# Hydroponics_Schematic.net
KiCad netlist of a schematic drawn in Altium Designer
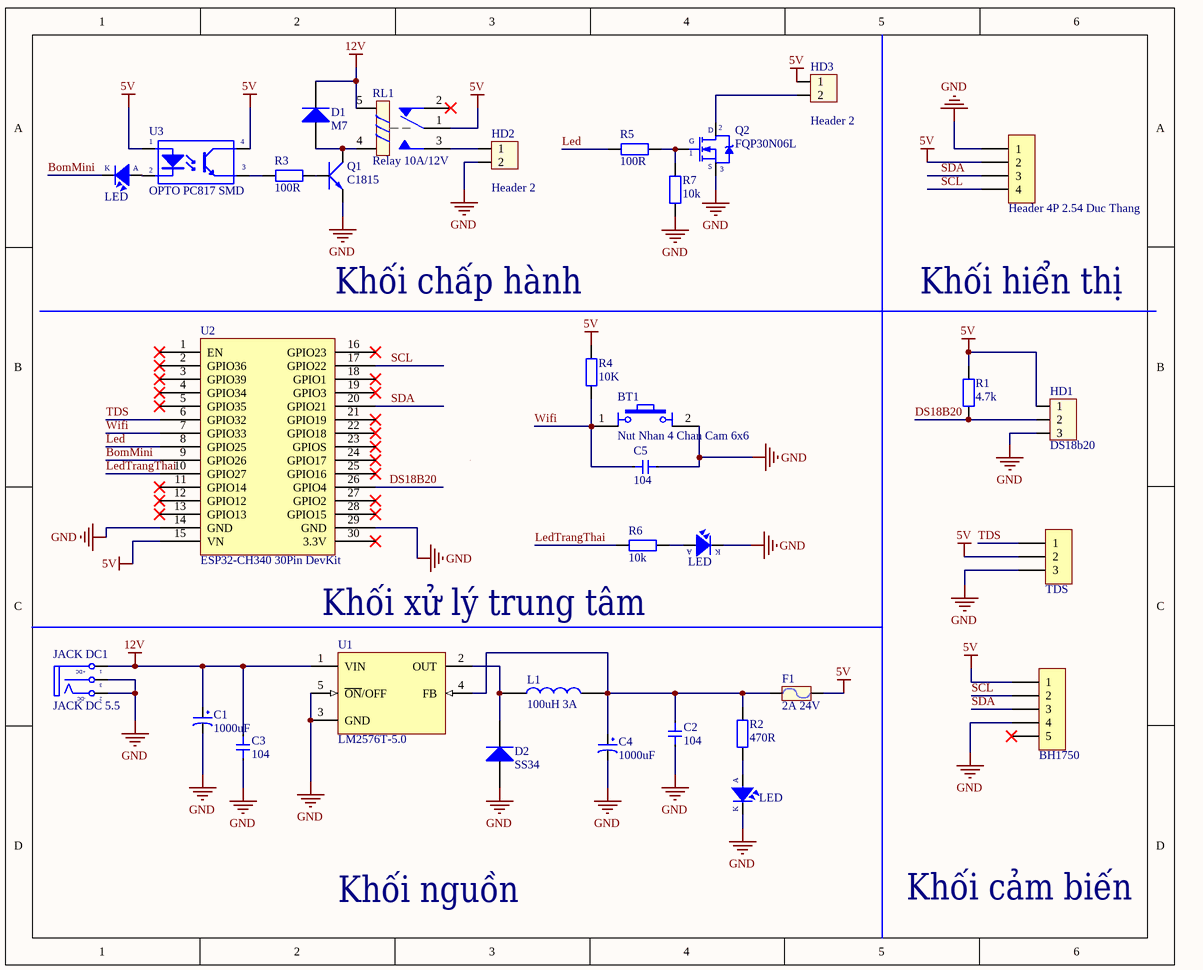
[diagram p0: Hydroponics_Schematic.SchDoc]

(export (version "E")
  (design (tool "Eeschema 10.0.6"))
  (components
    (comp (ref "BT1")
      (value "Nut Nhan 4 Chan Cam 6x6")
      (footprint "Nut Nhan 4 Chan Cam 6x6")
      (description "Nut Nhan 4 Chan 6x6mm")
      (libsource (lib "ThuvienAltiumFULLHD") (part "Nut Nhan 4 Chan Cam 6x6"))
    )
    (comp (ref "C1")
      (value "1000uF")
      (footprint "tu hoa 10mm")
      (description "Cắm")
      (libsource (lib "ThuvienAltiumFULLHD") (part "Tu Hoa 1000uF 10V 10x12"))
    )
    (comp (ref "C2")
      (value "104")
      (footprint "Cap 0805")
      (description "Capacitor SMD 0805")
      (libsource (lib "ThuvienAltiumFULLHD") (part "Cap 0805"))
    )
    (comp (ref "C3")
      (value "104")
      (footprint "Cap 0805")
      (description "Capacitor SMD 0805")
      (libsource (lib "ThuvienAltiumFULLHD") (part "Cap 0805"))
    )
    (comp (ref "C4")
      (value "1000uF")
      (footprint "tu hoa 10mm")
      (description "Cắm")
      (libsource (lib "ThuvienAltiumFULLHD") (part "Tu Hoa 1000uF 10V 10x12"))
    )
    (comp (ref "C5")
      (value "104")
      (footprint "Cap 0805")
      (description "Capacitor SMD 0805")
      (libsource (lib "ThuvienAltiumFULLHD") (part "Cap 0805"))
    )
    (comp (ref "D1")
      (value "M7")
      (footprint "DIODE SMA")
      (description "Dán")
      (libsource (lib "ThuvienAltiumFULLHD") (part "Diode M7 ( 4007 )"))
    )
    (comp (ref "D2")
      (value "SS34")
      (footprint "DIODE SMA")
      (description "Dán")
      (libsource (lib "ThuvienAltiumFULLHD") (part "Diode SS34 ( 1N5822 )"))
    )
    (comp (ref "F1")
      (value "2A 24V")
      (footprint "Cau chi tu phuc hoi 2A 24V SMD1812")
      (description "2A 24V SMD1812")
      (libsource (lib "ThuvienAltiumFULLHD") (part "Cau chi tu phuc hoi 2A 24V SMD1812"))
    )
    (comp (ref "H1")
      (value "BH1750")
      (footprint "XH2.54M-5")
      (description "Cắm")
      (libsource (lib "ThuvienAltiumFULLHD") (part "Header 5P 2.54 Duc Thang"))
    )
    (comp (ref "H2")
      (value "TDS")
      (footprint "XH2.54M-3")
      (description "Cắm")
      (libsource (lib "ThuvienAltiumFULLHD") (part "Header 3P 2.54 Duc Thang"))
    )
    (comp (ref "H3")
      (value "Header 4P 2.54 Duc Thang")
      (footprint "XH2.54M-4")
      (description "Cắm")
      (libsource (lib "ThuvienAltiumFULLHD") (part "Header 4P 2.54 Duc Thang"))
    )
    (comp (ref "HD1")
      (value "DS18b20")
      (footprint "KF127-3P")
      (description "Header 3 (Green)")
      (libsource (lib "PART_VDE") (part "Hed3"))
    )
    (comp (ref "HD2")
      (value "Header 2")
      (footprint "HED2")
      (description "Header 2 (Green)")
      (libsource (lib "PART_VDE") (part "Hed2"))
    )
    (comp (ref "HD3")
      (value "Header 2")
      (footprint "HED2")
      (description "Header 2 (Green)")
      (libsource (lib "PART_VDE") (part "Hed2"))
    )
    (comp (ref "JACK DC1")
      (value "JACK DC 5.5")
      (footprint "JACK DC 5.5")
      (libsource (lib "ThuvienAltiumFULLHD") (part "JACK DC 5.5"))
    )
    (comp (ref "L1")
      (value "100uH 3A")
      (footprint "CUON CAM 100uH3A")
      (description "Dán")
      (libsource (lib "ThuvienAltiumFULLHD") (part "CUON CAM 100uH DIP"))
    )
    (comp (ref "LED1")
      (value "LED")
      (footprint "LED-3")
      (description "LED Single colour Green and Red")
      (libsource (lib "ThuvienAltiumFULLHD") (part "LED"))
    )
    (comp (ref "LED2")
      (value "LED")
      (footprint "LED-3")
      (description "LED Single colour Green and Red")
      (libsource (lib "ThuvienAltiumFULLHD") (part "LED"))
    )
    (comp (ref "LED3")
      (value "LED")
      (footprint "LED-3")
      (description "LED Single colour Green and Red")
      (libsource (lib "ThuvienAltiumFULLHD") (part "LED"))
    )
    (comp (ref "Q1")
      (value "C1815")
      (footprint "QTO-92")
      (description "NPN 600mW, ECB")
      (libsource (lib "PART_VDE") (part "C1815"))
    )
    (comp (ref "Q2")
      (value "FQP30N06L")
      (footprint "QTO-220")
      (description "MOSFET N - CHANNEL 500V - 0.75 - 8A - TO-220")
      (libsource (lib "PART_VDE") (part "IRF840"))
    )
    (comp (ref "R1")
      (value "4.7k")
      (footprint "Tro SMD 0805")
      (description "Dán")
      (libsource (lib "ThuvienAltiumFULLHD") (part "Tro 0805 5% 470R"))
    )
    (comp (ref "R2")
      (value "470R")
      (footprint "Tro SMD 0805")
      (description "Dán")
      (libsource (lib "ThuvienAltiumFULLHD") (part "Tro 0805 5% 470R"))
    )
    (comp (ref "R3")
      (value "100R")
      (footprint "Tro SMD 0805")
      (description "Dán")
      (libsource (lib "ThuvienAltiumFULLHD") (part "Tro 0805 5% 470R"))
    )
    (comp (ref "R4")
      (value "10K")
      (footprint "Tro SMD 0805")
      (description "Dán")
      (libsource (lib "ThuvienAltiumFULLHD") (part "Tro 0805 5% 470R"))
    )
    (comp (ref "R5")
      (value "100R")
      (footprint "Tro SMD 0805")
      (description "Dán")
      (libsource (lib "ThuvienAltiumFULLHD") (part "Tro 0805 5% 470R"))
    )
    (comp (ref "R6")
      (value "10k")
      (footprint "Tro SMD 0805")
      (description "Dán")
      (libsource (lib "ThuvienAltiumFULLHD") (part "Tro 0805 5% 470R"))
    )
    (comp (ref "R7")
      (value "10k")
      (footprint "Tro SMD 0805")
      (description "Dán")
      (libsource (lib "ThuvienAltiumFULLHD") (part "Tro 0805 5% 470R"))
    )
    (comp (ref "RL1")
      (value "Relay 10A/12V")
      (footprint "RL_SPDT_10A")
      (description "Relay SPDT,10A - 12VDC 5 Pin")
      (libsource (lib "ThuvienAltiumFULLHD") (part "Relay 1"))
    )
    (comp (ref "U1")
      (value "LM2576T-5.0")
      (footprint "LM2576t")
      (description "SIMPLE SWITCHER; 3A Step-Down Voltage Regulator")
      (fields
        (field (name "MANUFACTURER") "National Semiconductor")
        (field (name "DIGIKEYPARTNUMBER") "LM2576T-5.0-ND")
        (field (name "PUBLISHER") "Altium Limited")
      )
      (libsource (lib "ThuvienAltiumFULLHD") (part "LM2576T-5.0"))
    )
    (comp (ref "U2")
      (value "ESP32-CH340 30Pin DevKit")
      (footprint "DIP30")
      (description "ESP32 DevKit V1 (CH340, 30 pins, 3.3V)")
      (libsource (lib "Schlib1") (part "Component_1"))
    )
    (comp (ref "U3")
      (value "OPTO PC817 SMD")
      (footprint "SOP4")
      (description "Single Opto")
      (libsource (lib "ThuvienAltiumFULLHD") (part "OPTO PC817 SMD"))
    )
  )
  (nets
    (net (code "1") (name "/BomMini") (class "Default")
      (node (ref "LED3") (pin "2") (pinfunction "K_2") (pintype "passive"))
      (node (ref "U2") (pin "9") (pinfunction "GPIO26_9") (pintype "passive"))
    )
    (net (code "2") (name "/DS18B20") (class "Default")
      (node (ref "HD1") (pin "2") (pinfunction "2_2") (pintype "passive"))
      (node (ref "R1") (pin "2") (pinfunction "2_2") (pintype "passive"))
      (node (ref "U2") (pin "26") (pinfunction "GPIO4_26") (pintype "passive"))
    )
    (net (code "3") (name "/Led") (class "Default")
      (node (ref "R5") (pin "1") (pinfunction "1_1") (pintype "passive"))
      (node (ref "U2") (pin "8") (pinfunction "GPIO25_8") (pintype "passive"))
    )
    (net (code "4") (name "/LedTrangThai") (class "Default")
      (node (ref "R6") (pin "2") (pinfunction "2_2") (pintype "passive"))
      (node (ref "U2") (pin "10") (pinfunction "GPIO27_10") (pintype "passive"))
    )
    (net (code "5") (name "/SCL") (class "Default")
      (node (ref "H1") (pin "2") (pinfunction "2_2") (pintype "passive"))
      (node (ref "H3") (pin "4") (pinfunction "4_4") (pintype "passive"))
      (node (ref "U2") (pin "17") (pinfunction "GPIO22_17") (pintype "passive"))
    )
    (net (code "6") (name "/SDA") (class "Default")
      (node (ref "H1") (pin "3") (pinfunction "3_3") (pintype "passive"))
      (node (ref "H3") (pin "3") (pinfunction "3_3") (pintype "passive"))
      (node (ref "U2") (pin "20") (pinfunction "GPIO21_20") (pintype "passive"))
    )
    (net (code "7") (name "/TDS") (class "Default")
      (node (ref "H2") (pin "1") (pinfunction "1_1") (pintype "passive"))
      (node (ref "U2") (pin "6") (pinfunction "GPIO32_6") (pintype "passive"))
    )
    (net (code "8") (name "/Wifi") (class "Default")
      (node (ref "BT1") (pin "1") (pintype "passive"))
      (node (ref "C5") (pin "1") (pinfunction "1_1") (pintype "passive"))
      (node (ref "R4") (pin "1") (pinfunction "1_1") (pintype "passive"))
      (node (ref "U2") (pin "7") (pinfunction "GPIO33_7") (pintype "passive"))
    )
    (net (code "9") (name "5V") (class "Default")
      (node (ref "F1") (pin "2") (pinfunction "2_2") (pintype "passive"))
      (node (ref "H1") (pin "1") (pinfunction "1_1") (pintype "passive"))
      (node (ref "H2") (pin "2") (pinfunction "2_2") (pintype "passive"))
      (node (ref "H3") (pin "2") (pinfunction "2_2") (pintype "passive"))
      (node (ref "HD1") (pin "1") (pinfunction "1_1") (pintype "passive"))
      (node (ref "HD3") (pin "1") (pinfunction "1_1") (pintype "passive"))
      (node (ref "R1") (pin "1") (pinfunction "1_1") (pintype "passive"))
      (node (ref "R4") (pin "2") (pinfunction "2_2") (pintype "passive"))
      (node (ref "RL1") (pin "1") (pinfunction "1_1") (pintype "passive"))
      (node (ref "U2") (pin "15") (pinfunction "VN_15") (pintype "passive"))
      (node (ref "U3") (pin "1") (pinfunction "A_1") (pintype "passive"))
      (node (ref "U3") (pin "4") (pinfunction "C_4") (pintype "passive"))
    )
    (net (code "10") (name "12V") (class "Default")
      (node (ref "C1") (pin "1") (pinfunction "1_1") (pintype "passive"))
      (node (ref "C3") (pin "1") (pinfunction "1_1") (pintype "passive"))
      (node (ref "D1") (pin "2") (pinfunction "K_2") (pintype "passive"))
      (node (ref "JACK DC1") (pin "1") (pinfunction "T_1") (pintype "passive"))
      (node (ref "RL1") (pin "5") (pinfunction "5_5") (pintype "passive"))
      (node (ref "U1") (pin "1") (pinfunction "VIN_1") (pintype "power_in"))
    )
    (net (code "11") (name "GND") (class "Default")
      (node (ref "BT1") (pin "2") (pintype "passive"))
      (node (ref "C1") (pin "2") (pinfunction "2_2") (pintype "passive"))
      (node (ref "C2") (pin "2") (pinfunction "2_2") (pintype "passive"))
      (node (ref "C3") (pin "2") (pinfunction "2_2") (pintype "passive"))
      (node (ref "C4") (pin "2") (pinfunction "2_2") (pintype "passive"))
      (node (ref "C5") (pin "2") (pinfunction "2_2") (pintype "passive"))
      (node (ref "D2") (pin "1") (pinfunction "A_1") (pintype "passive"))
      (node (ref "H1") (pin "4") (pinfunction "4_4") (pintype "passive"))
      (node (ref "H2") (pin "3") (pinfunction "3_3") (pintype "passive"))
      (node (ref "H3") (pin "1") (pinfunction "1_1") (pintype "passive"))
      (node (ref "HD1") (pin "3") (pinfunction "3_3") (pintype "passive"))
      (node (ref "HD2") (pin "2") (pinfunction "2_2") (pintype "passive"))
      (node (ref "JACK DC1") (pin "2") (pinfunction "TN_2") (pintype "passive"))
      (node (ref "JACK DC1") (pin "3") (pinfunction "S_3") (pintype "power_in"))
      (node (ref "LED1") (pin "2") (pinfunction "K_2") (pintype "passive"))
      (node (ref "LED2") (pin "2") (pinfunction "K_2") (pintype "passive"))
      (node (ref "Q1") (pin "1") (pinfunction "E_1") (pintype "passive"))
      (node (ref "Q2") (pin "3") (pinfunction "S_3") (pintype "passive"))
      (node (ref "R7") (pin "2") (pinfunction "2_2") (pintype "passive"))
      (node (ref "U1") (pin "3") (pinfunction "GND_3") (pintype "power_in"))
      (node (ref "U1") (pin "5") (pinfunction "~{ON}/OFF_5") (pintype "input"))
      (node (ref "U2") (pin "14") (pinfunction "GND_14") (pintype "passive"))
      (node (ref "U2") (pin "29") (pinfunction "GND_29") (pintype "passive"))
    )
    (net (code "12") (name "Net-(D1-A)") (class "Default")
      (node (ref "D1") (pin "1") (pinfunction "A_1") (pintype "passive"))
      (node (ref "Q1") (pin "2") (pinfunction "C_2") (pintype "passive"))
      (node (ref "RL1") (pin "4") (pinfunction "4_4") (pintype "passive"))
    )
    (net (code "13") (name "Net-(D2-K)") (class "Default")
      (node (ref "D2") (pin "2") (pinfunction "K_2") (pintype "passive"))
      (node (ref "L1") (pin "1") (pinfunction "1_1") (pintype "passive"))
      (node (ref "U1") (pin "2") (pinfunction "OUT_2") (pintype "power_in"))
    )
    (net (code "14") (name "Net-(HD2-Pad1)") (class "Default")
      (node (ref "HD2") (pin "1") (pinfunction "1_1") (pintype "passive"))
      (node (ref "RL1") (pin "3") (pinfunction "3_3") (pintype "passive"))
    )
    (net (code "15") (name "Net-(LED1-A)") (class "Default")
      (node (ref "LED1") (pin "1") (pinfunction "A_1") (pintype "passive"))
      (node (ref "R2") (pin "1") (pinfunction "1_1") (pintype "passive"))
    )
    (net (code "16") (name "Net-(LED2-A)") (class "Default")
      (node (ref "LED2") (pin "1") (pinfunction "A_1") (pintype "passive"))
      (node (ref "R6") (pin "1") (pinfunction "1_1") (pintype "passive"))
    )
    (net (code "17") (name "Net-(LED3-A)") (class "Default")
      (node (ref "LED3") (pin "1") (pinfunction "A_1") (pintype "passive"))
      (node (ref "U3") (pin "2") (pinfunction "K_2") (pintype "passive"))
    )
    (net (code "18") (name "Net-(Q1-B)") (class "Default")
      (node (ref "Q1") (pin "3") (pinfunction "B_3") (pintype "passive"))
      (node (ref "R3") (pin "2") (pinfunction "2_2") (pintype "passive"))
    )
    (net (code "19") (name "Net-(Q2-D)") (class "Default")
      (node (ref "HD3") (pin "2") (pinfunction "2_2") (pintype "passive"))
      (node (ref "Q2") (pin "2") (pinfunction "D_2") (pintype "passive"))
    )
    (net (code "20") (name "Net-(Q2-G)") (class "Default")
      (node (ref "Q2") (pin "1") (pinfunction "G_1") (pintype "passive"))
      (node (ref "R5") (pin "2") (pinfunction "2_2") (pintype "passive"))
      (node (ref "R7") (pin "1") (pinfunction "1_1") (pintype "passive"))
    )
    (net (code "21") (name "Net-(U1-FB)") (class "Default")
      (node (ref "C2") (pin "1") (pinfunction "1_1") (pintype "passive"))
      (node (ref "C4") (pin "1") (pinfunction "1_1") (pintype "passive"))
      (node (ref "F1") (pin "1") (pinfunction "1_1") (pintype "passive"))
      (node (ref "L1") (pin "2") (pinfunction "2_2") (pintype "passive"))
      (node (ref "R2") (pin "2") (pinfunction "2_2") (pintype "passive"))
      (node (ref "U1") (pin "4") (pinfunction "FB_4") (pintype "input"))
    )
    (net (code "22") (name "Net-(U3-E)") (class "Default")
      (node (ref "R3") (pin "1") (pinfunction "1_1") (pintype "passive"))
      (node (ref "U3") (pin "3") (pinfunction "E_3") (pintype "passive"))
    )
    (net (code "23") (name "unconnected-(H1-Pad5)") (class "Default")
      (node (ref "H1") (pin "5") (pinfunction "5_5") (pintype "passive+no_connect"))
    )
    (net (code "24") (name "unconnected-(RL1-Pad2)") (class "Default")
      (node (ref "RL1") (pin "2") (pinfunction "2_2") (pintype "passive+no_connect"))
    )
    (net (code "25") (name "unconnected-(U2-3.3V-Pad30)") (class "Default")
      (node (ref "U2") (pin "30") (pinfunction "3.3V_30") (pintype "passive+no_connect"))
    )
    (net (code "26") (name "unconnected-(U2-EN-Pad1)") (class "Default")
      (node (ref "U2") (pin "1") (pinfunction "EN_1") (pintype "passive+no_connect"))
    )
    (net (code "27") (name "unconnected-(U2-GPIO1-Pad18)") (class "Default")
      (node (ref "U2") (pin "18") (pinfunction "GPIO1_18") (pintype "passive+no_connect"))
    )
    (net (code "28") (name "unconnected-(U2-GPIO2-Pad27)") (class "Default")
      (node (ref "U2") (pin "27") (pinfunction "GPIO2_27") (pintype "passive+no_connect"))
    )
    (net (code "29") (name "unconnected-(U2-GPIO3-Pad19)") (class "Default")
      (node (ref "U2") (pin "19") (pinfunction "GPIO3_19") (pintype "passive+no_connect"))
    )
    (net (code "30") (name "unconnected-(U2-GPIO12-Pad12)") (class "Default")
      (node (ref "U2") (pin "12") (pinfunction "GPIO12_12") (pintype "passive+no_connect"))
    )
    (net (code "31") (name "unconnected-(U2-GPIO13-Pad13)") (class "Default")
      (node (ref "U2") (pin "13") (pinfunction "GPIO13_13") (pintype "passive+no_connect"))
    )
    (net (code "32") (name "unconnected-(U2-GPIO14-Pad11)") (class "Default")
      (node (ref "U2") (pin "11") (pinfunction "GPIO14_11") (pintype "passive+no_connect"))
    )
    (net (code "33") (name "unconnected-(U2-GPIO15-Pad28)") (class "Default")
      (node (ref "U2") (pin "28") (pinfunction "GPIO15_28") (pintype "passive+no_connect"))
    )
    (net (code "34") (name "unconnected-(U2-GPIO16-Pad25)") (class "Default")
      (node (ref "U2") (pin "25") (pinfunction "GPIO16_25") (pintype "passive+no_connect"))
    )
    (net (code "35") (name "unconnected-(U2-GPIO17-Pad24)") (class "Default")
      (node (ref "U2") (pin "24") (pinfunction "GPIO17_24") (pintype "passive+no_connect"))
    )
    (net (code "36") (name "unconnected-(U2-GPIO18-Pad22)") (class "Default")
      (node (ref "U2") (pin "22") (pinfunction "GPIO18_22") (pintype "passive+no_connect"))
    )
    (net (code "37") (name "unconnected-(U2-GPIO19-Pad21)") (class "Default")
      (node (ref "U2") (pin "21") (pinfunction "GPIO19_21") (pintype "passive+no_connect"))
    )
    (net (code "38") (name "unconnected-(U2-GPIO23-Pad16)") (class "Default")
      (node (ref "U2") (pin "16") (pinfunction "GPIO23_16") (pintype "passive+no_connect"))
    )
    (net (code "39") (name "unconnected-(U2-GPIO34-Pad4)") (class "Default")
      (node (ref "U2") (pin "4") (pinfunction "GPIO34_4") (pintype "passive+no_connect"))
    )
    (net (code "40") (name "unconnected-(U2-GPIO35-Pad5)") (class "Default")
      (node (ref "U2") (pin "5") (pinfunction "GPIO35_5") (pintype "passive+no_connect"))
    )
    (net (code "41") (name "unconnected-(U2-GPIO36-Pad2)") (class "Default")
      (node (ref "U2") (pin "2") (pinfunction "GPIO36_2") (pintype "passive+no_connect"))
    )
    (net (code "42") (name "unconnected-(U2-GPIO39-Pad3)") (class "Default")
      (node (ref "U2") (pin "3") (pinfunction "GPIO39_3") (pintype "passive+no_connect"))
    )
    (net (code "43") (name "unconnected-(U2-GPIOS-Pad23)") (class "Default")
      (node (ref "U2") (pin "23") (pinfunction "GPIOS_23") (pintype "passive+no_connect"))
    )
  )
)
